# gauge_final.net
KiCad netlist of a schematic drawn in EAGLE
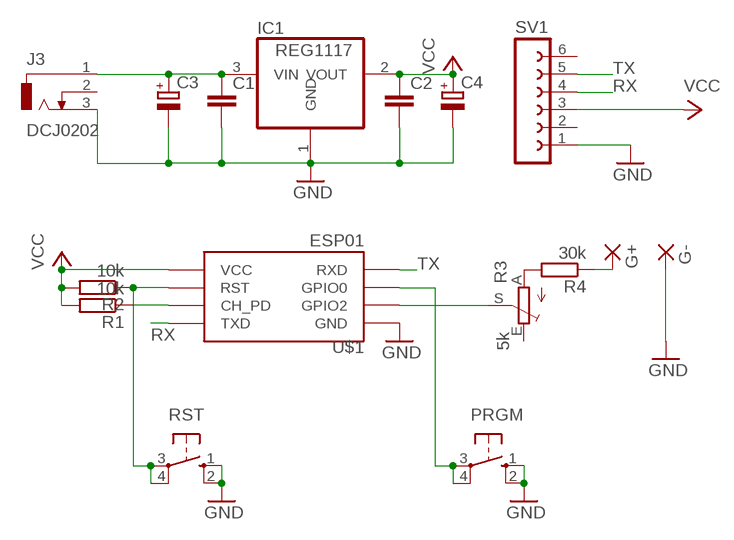
[diagram p0: schematic, sheet 1]

(export (version "E")
  (design (tool "Eeschema 10.0.6"))
  (components
    (comp (ref "C1")
      (value "C-EUC0805")
      (footprint "eagle-import:C0805")
      (libsource (lib "eagle-import") (part "C-EUC0805"))
    )
    (comp (ref "C2")
      (value "C-EUC0805")
      (footprint "eagle-import:C0805")
      (libsource (lib "eagle-import") (part "C-EUC0805"))
    )
    (comp (ref "C3")
      (value "CPOL-EUSMCE")
      (footprint "eagle-import:SMC_E")
      (libsource (lib "eagle-import") (part "CPOL-EUSMCE"))
    )
    (comp (ref "C4")
      (value "CPOL-EUSMCE")
      (footprint "eagle-import:SMC_E")
      (libsource (lib "eagle-import") (part "CPOL-EUSMCE"))
    )
    (comp (ref "G+")
      (value "3,81/1,4")
      (footprint "eagle-import:3,81_1,4")
      (libsource (lib "eagle-import") (part "3,81/1,4"))
    )
    (comp (ref "G-")
      (value "3,81/1,4")
      (footprint "eagle-import:3,81_1,4")
      (libsource (lib "eagle-import") (part "3,81/1,4"))
    )
    (comp (ref "IC1")
      (value "REG1117")
      (footprint "eagle-import:SOT223")
      (libsource (lib "eagle-import") (part "REG1117"))
    )
    (comp (ref "J3")
      (value "DCJ0202")
      (footprint "eagle-import:DCJ0202")
      (libsource (lib "eagle-import") (part "DCJ0202"))
    )
    (comp (ref "PRGM")
      (value "10-XX")
      (footprint "eagle-import:B3F-10XX")
      (fields (field (name "MPN") "B3F-1000"))
      (libsource (lib "eagle-import") (part "10-XX"))
    )
    (comp (ref "R1")
      (value "10k")
      (footprint "eagle-import:R0805")
      (libsource (lib "eagle-import") (part "R-EU_R0805"))
    )
    (comp (ref "R2")
      (value "10k")
      (footprint "eagle-import:R0805")
      (libsource (lib "eagle-import") (part "R-EU_R0805"))
    )
    (comp (ref "R3")
      (value "5k")
      (footprint "eagle-import:SP19L")
      (libsource (lib "eagle-import") (part "TRIM_EU-B90P"))
    )
    (comp (ref "R4")
      (value "30k")
      (footprint "eagle-import:R0805")
      (libsource (lib "eagle-import") (part "R-EU_R0805"))
    )
    (comp (ref "RST")
      (value "10-XX")
      (footprint "eagle-import:B3F-10XX")
      (fields (field (name "MPN") "B3F-1000"))
      (libsource (lib "eagle-import") (part "10-XX"))
    )
    (comp (ref "SV1")
      (value "FE06-1")
      (footprint "eagle-import:FE06")
      (libsource (lib "eagle-import") (part "FE06-1"))
    )
    (comp (ref "U$1")
      (value "ESP01")
      (footprint "eagle-import:ESP01")
      (libsource (lib "eagle-import") (part "ESP01"))
    )
  )
  (nets
    (net (code "1") (name "/RX") (class "Default")
      (node (ref "SV1") (pin "4") (pinfunction "4_4") (pintype "passive"))
      (node (ref "U$1") (pin "TX") (pinfunction "TXD_TX") (pintype "bidirectional"))
    )
    (net (code "2") (name "/TX") (class "Default")
      (node (ref "SV1") (pin "5") (pinfunction "5_5") (pintype "passive"))
      (node (ref "U$1") (pin "RX") (pinfunction "RXD_RX") (pintype "bidirectional"))
    )
    (net (code "3") (name "GND") (class "Default")
      (node (ref "C1") (pin "2") (pinfunction "2_2") (pintype "passive"))
      (node (ref "C2") (pin "2") (pinfunction "2_2") (pintype "passive"))
      (node (ref "C3") (pin "-") (pinfunction "-_-") (pintype "passive"))
      (node (ref "C4") (pin "-") (pinfunction "-_-") (pintype "passive"))
      (node (ref "G-") (pin "1") (pinfunction "P_1") (pintype "passive"))
      (node (ref "IC1") (pin "1") (pinfunction "GND_1") (pintype "power_in"))
      (node (ref "J3") (pin "3") (pinfunction "3_3") (pintype "passive"))
      (node (ref "PRGM") (pin "1") (pinfunction "S_1") (pintype "passive"))
      (node (ref "PRGM") (pin "2") (pinfunction "S1_2") (pintype "passive"))
      (node (ref "RST") (pin "1") (pinfunction "S_1") (pintype "passive"))
      (node (ref "RST") (pin "2") (pinfunction "S1_2") (pintype "passive"))
      (node (ref "SV1") (pin "1") (pinfunction "1_1") (pintype "passive"))
      (node (ref "U$1") (pin "GND") (pinfunction "GND_GND") (pintype "bidirectional"))
    )
    (net (code "4") (name "Net-(G+-P)") (class "Default")
      (node (ref "G+") (pin "1") (pinfunction "P_1") (pintype "passive"))
      (node (ref "R4") (pin "1") (pinfunction "1_1") (pintype "passive"))
    )
    (net (code "5") (name "Net-(IC1-VIN)") (class "Default")
      (node (ref "C1") (pin "1") (pinfunction "1_1") (pintype "passive"))
      (node (ref "C3") (pin "+") (pinfunction "+_+") (pintype "passive"))
      (node (ref "IC1") (pin "3") (pinfunction "VIN_3") (pintype "input"))
      (node (ref "J3") (pin "1") (pinfunction "1_1") (pintype "passive"))
    )
    (net (code "6") (name "Net-(PRGM-P)") (class "Default")
      (node (ref "PRGM") (pin "3") (pinfunction "P_3") (pintype "passive"))
      (node (ref "PRGM") (pin "4") (pinfunction "P1_4") (pintype "passive"))
      (node (ref "U$1") (pin "GPIO0") (pinfunction "GPIO0_GPIO0") (pintype "bidirectional"))
    )
    (net (code "7") (name "Net-(R1-Pad1)") (class "Default")
      (node (ref "R1") (pin "1") (pinfunction "1_1") (pintype "passive"))
      (node (ref "U$1") (pin "CH_PD") (pinfunction "CH_PD_CH_PD") (pintype "bidirectional"))
    )
    (net (code "8") (name "Net-(R3-PadA)") (class "Default")
      (node (ref "R3") (pin "A") (pinfunction "A_A") (pintype "passive"))
      (node (ref "R4") (pin "2") (pinfunction "2_2") (pintype "passive"))
    )
    (net (code "9") (name "Net-(R3-PadS)") (class "Default")
      (node (ref "R3") (pin "S") (pinfunction "S_S") (pintype "passive"))
      (node (ref "U$1") (pin "GPIO2") (pinfunction "GPIO2_GPIO2") (pintype "bidirectional"))
    )
    (net (code "10") (name "Net-(RST-P)") (class "Default")
      (node (ref "R2") (pin "1") (pinfunction "1_1") (pintype "passive"))
      (node (ref "RST") (pin "3") (pinfunction "P_3") (pintype "passive"))
      (node (ref "RST") (pin "4") (pinfunction "P1_4") (pintype "passive"))
      (node (ref "U$1") (pin "RST") (pinfunction "RST_RST") (pintype "bidirectional"))
    )
    (net (code "11") (name "VCC") (class "Default")
      (node (ref "C2") (pin "1") (pinfunction "1_1") (pintype "passive"))
      (node (ref "C4") (pin "+") (pinfunction "+_+") (pintype "passive"))
      (node (ref "IC1") (pin "2") (pinfunction "VOUT_2") (pintype "output"))
      (node (ref "R1") (pin "2") (pinfunction "2_2") (pintype "passive"))
      (node (ref "R2") (pin "2") (pinfunction "2_2") (pintype "passive"))
      (node (ref "SV1") (pin "3") (pinfunction "3_3") (pintype "passive"))
      (node (ref "U$1") (pin "VCC") (pinfunction "VCC_VCC") (pintype "bidirectional"))
    )
    (net (code "12") (name "unconnected-(J3-Pad2)") (class "Default")
      (node (ref "J3") (pin "2") (pinfunction "2_2") (pintype "passive"))
    )
    (net (code "13") (name "unconnected-(R3-PadE)") (class "Default")
      (node (ref "R3") (pin "E") (pinfunction "E_E") (pintype "passive"))
    )
    (net (code "14") (name "unconnected-(SV1-Pad2)") (class "Default")
      (node (ref "SV1") (pin "2") (pinfunction "2_2") (pintype "passive"))
    )
    (net (code "15") (name "unconnected-(SV1-Pad6)") (class "Default")
      (node (ref "SV1") (pin "6") (pinfunction "6_6") (pintype "passive"))
    )
  )
)
